# prototype.net
KiCad netlist of a schematic drawn in EAGLE
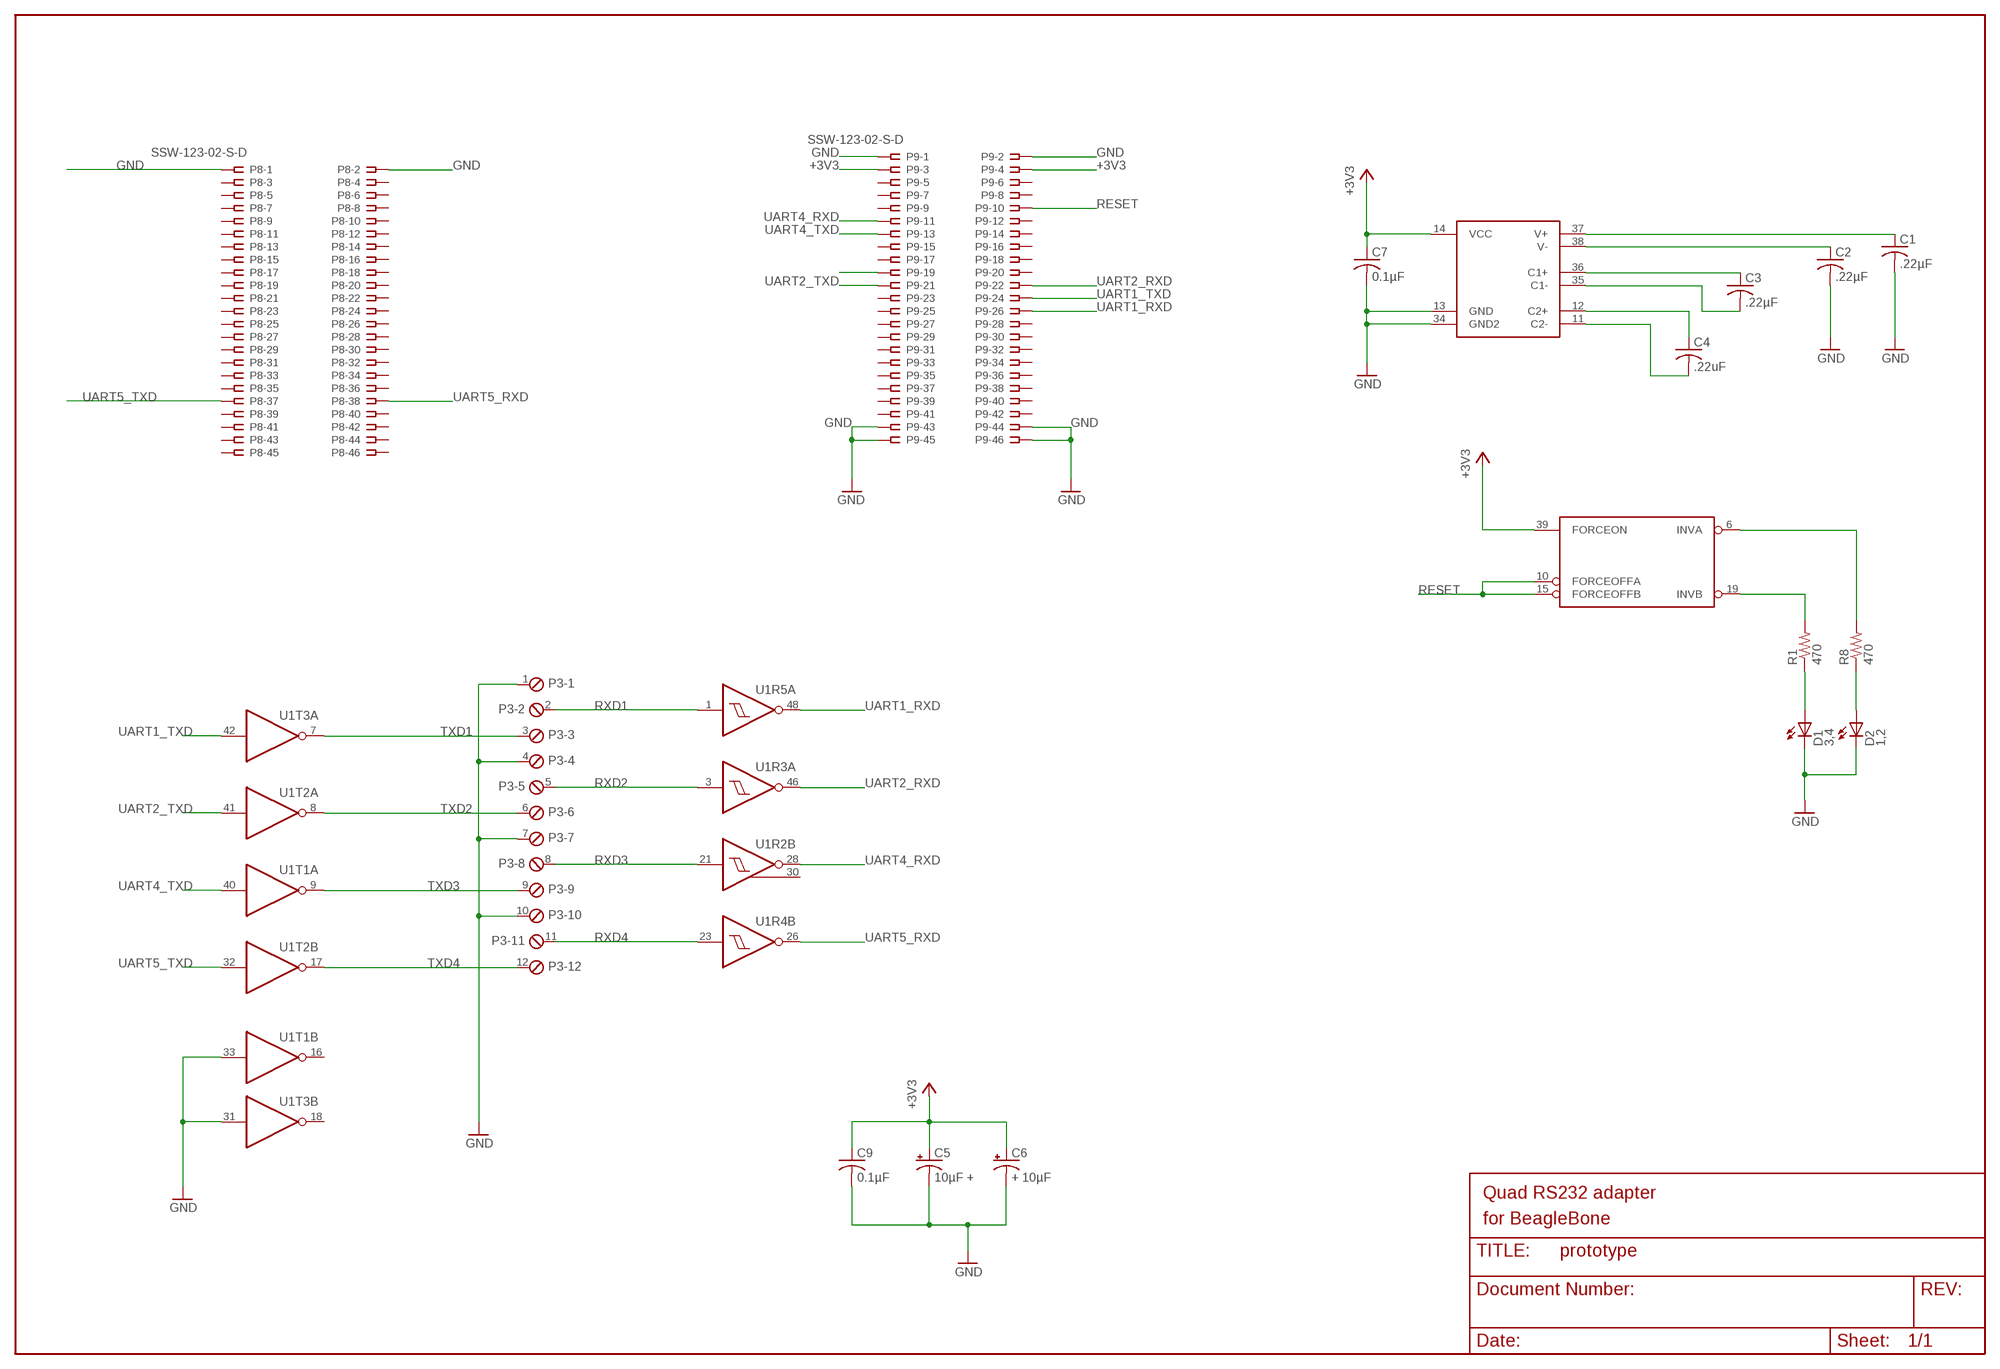
[diagram p0: schematic, sheet 1]

(export (version "E")
  (design (tool "Eeschema 10.0.6"))
  (components
    (comp (ref "C1")
      (value ".22µF")
      (footprint "eagle-import:C0603")
      (libsource (lib "eagle-import") (part "C-USC0603"))
    )
    (comp (ref "C2")
      (value ".22µF")
      (footprint "eagle-import:C0603")
      (libsource (lib "eagle-import") (part "C-USC0603"))
    )
    (comp (ref "C3")
      (value ".22µF")
      (footprint "eagle-import:C0603")
      (libsource (lib "eagle-import") (part "C-USC0603"))
    )
    (comp (ref "C4")
      (value ".22uF")
      (footprint "eagle-import:C0603")
      (libsource (lib "eagle-import") (part "C-USC0603"))
    )
    (comp (ref "C5")
      (value "10µF +")
      (footprint "eagle-import:C1206")
      (libsource (lib "eagle-import") (part "CPOL-USC1206"))
    )
    (comp (ref "C6")
      (value "+ 10µF")
      (footprint "eagle-import:C1206")
      (libsource (lib "eagle-import") (part "CPOL-USC1206"))
    )
    (comp (ref "C7")
      (value "0.1µF")
      (footprint "eagle-import:C0603")
      (libsource (lib "eagle-import") (part "C-USC0603"))
    )
    (comp (ref "C9")
      (value "0.1µF")
      (footprint "eagle-import:C0603")
      (libsource (lib "eagle-import") (part "C-USC0603"))
    )
    (comp (ref "D1")
      (value "3,4")
      (footprint "eagle-import:CHIPLED_0603")
      (libsource (lib "eagle-import") (part "LEDCHIPLED_0603"))
    )
    (comp (ref "D2")
      (value "1,2")
      (footprint "eagle-import:CHIPLED_0603")
      (libsource (lib "eagle-import") (part "LEDCHIPLED_0603"))
    )
    (comp (ref "P3")
      (value "MPT12")
      (footprint "eagle-import:12POL254")
      (libsource (lib "eagle-import") (part "MPT12"))
    )
    (comp (ref "P8")
      (value "SSW-123-02-S-D")
      (footprint "eagle-import:SSW-123-02-S-D")
      (libsource (lib "eagle-import") (part "SSW-123-02-S-D"))
    )
    (comp (ref "P9")
      (value "SSW-123-02-S-D")
      (footprint "eagle-import:SSW-123-02-S-D")
      (libsource (lib "eagle-import") (part "SSW-123-02-S-D"))
    )
    (comp (ref "R1")
      (value "470")
      (footprint "eagle-import:R0603")
      (libsource (lib "eagle-import") (part "R-US_R0603"))
    )
    (comp (ref "R8")
      (value "470")
      (footprint "eagle-import:R0603")
      (libsource (lib "eagle-import") (part "R-US_R0603"))
    )
    (comp (ref "U1")
      (value "SN75C23243")
      (footprint "eagle-import:SSOP48DL")
      (libsource (lib "eagle-import") (part "SN75C23243SN75C23243DL"))
    )
  )
  (nets
    (net (code "1") (name "+3V3") (class "Default")
      (node (ref "C5") (pin "1") (pinfunction "+_1") (pintype "passive"))
      (node (ref "C6") (pin "1") (pinfunction "+_1") (pintype "passive"))
      (node (ref "C7") (pin "1") (pinfunction "1_1") (pintype "passive"))
      (node (ref "C9") (pin "1") (pinfunction "1_1") (pintype "passive"))
      (node (ref "P9") (pin "3") (pinfunction "1_3") (pintype "passive"))
      (node (ref "P9") (pin "4") (pinfunction "1_4") (pintype "passive"))
      (node (ref "U1") (pin "14") (pinfunction "VCC_14") (pintype "power_in"))
      (node (ref "U1") (pin "39") (pinfunction "FORCEON_39") (pintype "input"))
    )
    (net (code "2") (name "/RESET") (class "Default")
      (node (ref "P9") (pin "10") (pinfunction "1_10") (pintype "passive"))
      (node (ref "U1") (pin "10") (pinfunction "FORCEOFFA_10") (pintype "input"))
      (node (ref "U1") (pin "15") (pinfunction "FORCEOFFB_15") (pintype "input"))
    )
    (net (code "3") (name "/RXD1") (class "Default")
      (node (ref "P3") (pin "2") (pinfunction "1_2") (pintype "passive"))
      (node (ref "U1") (pin "1") (pinfunction "I_1") (pintype "input"))
    )
    (net (code "4") (name "/RXD2") (class "Default")
      (node (ref "P3") (pin "5") (pinfunction "1_5") (pintype "passive"))
      (node (ref "U1") (pin "3") (pinfunction "I_3") (pintype "input"))
    )
    (net (code "5") (name "/RXD3") (class "Default")
      (node (ref "P3") (pin "8") (pinfunction "1_8") (pintype "passive"))
      (node (ref "U1") (pin "21") (pinfunction "I_21") (pintype "input"))
    )
    (net (code "6") (name "/RXD4") (class "Default")
      (node (ref "P3") (pin "11") (pinfunction "1_11") (pintype "passive"))
      (node (ref "U1") (pin "23") (pinfunction "I_23") (pintype "input"))
    )
    (net (code "7") (name "/TXD1") (class "Default")
      (node (ref "P3") (pin "3") (pinfunction "1_3") (pintype "passive"))
      (node (ref "U1") (pin "7") (pinfunction "O_7") (pintype "output"))
    )
    (net (code "8") (name "/TXD2") (class "Default")
      (node (ref "P3") (pin "6") (pinfunction "1_6") (pintype "passive"))
      (node (ref "U1") (pin "8") (pinfunction "O_8") (pintype "output"))
    )
    (net (code "9") (name "/TXD3") (class "Default")
      (node (ref "P3") (pin "9") (pinfunction "1_9") (pintype "passive"))
      (node (ref "U1") (pin "9") (pinfunction "O_9") (pintype "output"))
    )
    (net (code "10") (name "/TXD4") (class "Default")
      (node (ref "P3") (pin "12") (pinfunction "1_12") (pintype "passive"))
      (node (ref "U1") (pin "17") (pinfunction "O_17") (pintype "output"))
    )
    (net (code "11") (name "/UART1_RXD") (class "Default")
      (node (ref "P9") (pin "26") (pinfunction "1_26") (pintype "passive"))
      (node (ref "U1") (pin "48") (pinfunction "O_48") (pintype "output"))
    )
    (net (code "12") (name "/UART1_TXD") (class "Default")
      (node (ref "P9") (pin "24") (pinfunction "1_24") (pintype "passive"))
      (node (ref "U1") (pin "42") (pinfunction "I_42") (pintype "input"))
    )
    (net (code "13") (name "/UART2_RXD") (class "Default")
      (node (ref "P9") (pin "22") (pinfunction "1_22") (pintype "passive"))
      (node (ref "U1") (pin "46") (pinfunction "O_46") (pintype "output"))
    )
    (net (code "14") (name "/UART2_TXD") (class "Default")
      (node (ref "P9") (pin "21") (pinfunction "1_21") (pintype "passive"))
      (node (ref "U1") (pin "41") (pinfunction "I_41") (pintype "input"))
    )
    (net (code "15") (name "/UART4_RXD") (class "Default")
      (node (ref "P9") (pin "11") (pinfunction "1_11") (pintype "passive"))
      (node (ref "U1") (pin "28") (pinfunction "O_28") (pintype "output"))
    )
    (net (code "16") (name "/UART4_TXD") (class "Default")
      (node (ref "P9") (pin "13") (pinfunction "1_13") (pintype "passive"))
      (node (ref "U1") (pin "40") (pinfunction "I_40") (pintype "input"))
    )
    (net (code "17") (name "/UART5_RXD") (class "Default")
      (node (ref "P8") (pin "38") (pinfunction "1_38") (pintype "passive"))
      (node (ref "U1") (pin "26") (pinfunction "O_26") (pintype "output"))
    )
    (net (code "18") (name "/UART5_TXD") (class "Default")
      (node (ref "P8") (pin "37") (pinfunction "1_37") (pintype "passive"))
      (node (ref "U1") (pin "32") (pinfunction "I_32") (pintype "input"))
    )
    (net (code "19") (name "GND") (class "Default")
      (node (ref "C1") (pin "2") (pinfunction "2_2") (pintype "passive"))
      (node (ref "C2") (pin "2") (pinfunction "2_2") (pintype "passive"))
      (node (ref "C5") (pin "2") (pinfunction "-_2") (pintype "passive"))
      (node (ref "C6") (pin "2") (pinfunction "-_2") (pintype "passive"))
      (node (ref "C7") (pin "2") (pinfunction "2_2") (pintype "passive"))
      (node (ref "C9") (pin "2") (pinfunction "2_2") (pintype "passive"))
      (node (ref "D1") (pin "C") (pinfunction "C_C") (pintype "passive"))
      (node (ref "D2") (pin "C") (pinfunction "C_C") (pintype "passive"))
      (node (ref "P3") (pin "1") (pinfunction "1_1") (pintype "passive"))
      (node (ref "P3") (pin "10") (pinfunction "1_10") (pintype "passive"))
      (node (ref "P3") (pin "4") (pinfunction "1_4") (pintype "passive"))
      (node (ref "P3") (pin "7") (pinfunction "1_7") (pintype "passive"))
      (node (ref "P8") (pin "1") (pinfunction "1_1") (pintype "passive"))
      (node (ref "P8") (pin "2") (pinfunction "1_2") (pintype "passive"))
      (node (ref "P9") (pin "1") (pinfunction "1_1") (pintype "passive"))
      (node (ref "P9") (pin "2") (pinfunction "1_2") (pintype "passive"))
      (node (ref "P9") (pin "43") (pinfunction "1_43") (pintype "passive"))
      (node (ref "P9") (pin "44") (pinfunction "1_44") (pintype "passive"))
      (node (ref "P9") (pin "45") (pinfunction "1_45") (pintype "passive"))
      (node (ref "P9") (pin "46") (pinfunction "1_46") (pintype "passive"))
      (node (ref "U1") (pin "13") (pinfunction "GND_13") (pintype "power_in"))
      (node (ref "U1") (pin "31") (pinfunction "I_31") (pintype "input"))
      (node (ref "U1") (pin "33") (pinfunction "I_33") (pintype "input"))
      (node (ref "U1") (pin "34") (pinfunction "GND2_34") (pintype "power_in"))
    )
    (net (code "20") (name "Net-(D1-PadA)") (class "Default")
      (node (ref "D1") (pin "A") (pinfunction "A_A") (pintype "passive"))
      (node (ref "R1") (pin "1") (pinfunction "1_1") (pintype "passive"))
    )
    (net (code "21") (name "Net-(D2-PadA)") (class "Default")
      (node (ref "D2") (pin "A") (pinfunction "A_A") (pintype "passive"))
      (node (ref "R8") (pin "1") (pinfunction "1_1") (pintype "passive"))
    )
    (net (code "22") (name "Net-(U1A-INVA)") (class "Default")
      (node (ref "R8") (pin "2") (pinfunction "2_2") (pintype "passive"))
      (node (ref "U1") (pin "6") (pinfunction "INVA_6") (pintype "output"))
    )
    (net (code "23") (name "Net-(U1A-INVB)") (class "Default")
      (node (ref "R1") (pin "2") (pinfunction "2_2") (pintype "passive"))
      (node (ref "U1") (pin "19") (pinfunction "INVB_19") (pintype "output"))
    )
    (net (code "24") (name "Net-(U1B-C1+)") (class "Default")
      (node (ref "C3") (pin "1") (pinfunction "1_1") (pintype "passive"))
      (node (ref "U1") (pin "36") (pinfunction "C1+_36") (pintype "power_in"))
    )
    (net (code "25") (name "Net-(U1B-C1-)") (class "Default")
      (node (ref "C3") (pin "2") (pinfunction "2_2") (pintype "passive"))
      (node (ref "U1") (pin "35") (pinfunction "C1-_35") (pintype "power_in"))
    )
    (net (code "26") (name "Net-(U1B-C2+)") (class "Default")
      (node (ref "C4") (pin "1") (pinfunction "1_1") (pintype "passive"))
      (node (ref "U1") (pin "12") (pinfunction "C2+_12") (pintype "power_in"))
    )
    (net (code "27") (name "Net-(U1B-C2-)") (class "Default")
      (node (ref "C4") (pin "2") (pinfunction "2_2") (pintype "passive"))
      (node (ref "U1") (pin "11") (pinfunction "C2-_11") (pintype "power_in"))
    )
    (net (code "28") (name "Net-(U1B-V+)") (class "Default")
      (node (ref "C1") (pin "1") (pinfunction "1_1") (pintype "passive"))
      (node (ref "U1") (pin "37") (pinfunction "V+_37") (pintype "power_in"))
    )
    (net (code "29") (name "Net-(U1B-V-)") (class "Default")
      (node (ref "C2") (pin "1") (pinfunction "1_1") (pintype "passive"))
      (node (ref "U1") (pin "38") (pinfunction "V-_38") (pintype "power_in"))
    )
    (net (code "30") (name "unconnected-(P8AA-1-Pad33)") (class "Default")
      (node (ref "P8") (pin "33") (pinfunction "1_33") (pintype "passive"))
    )
    (net (code "31") (name "unconnected-(P8AB-1-Pad34)") (class "Default")
      (node (ref "P8") (pin "34") (pinfunction "1_34") (pintype "passive"))
    )
    (net (code "32") (name "unconnected-(P8AC-1-Pad35)") (class "Default")
      (node (ref "P8") (pin "35") (pinfunction "1_35") (pintype "passive"))
    )
    (net (code "33") (name "unconnected-(P8AD-1-Pad36)") (class "Default")
      (node (ref "P8") (pin "36") (pinfunction "1_36") (pintype "passive"))
    )
    (net (code "34") (name "unconnected-(P8AG-1-Pad39)") (class "Default")
      (node (ref "P8") (pin "39") (pinfunction "1_39") (pintype "passive"))
    )
    (net (code "35") (name "unconnected-(P8AH-1-Pad4)") (class "Default")
      (node (ref "P8") (pin "4") (pinfunction "1_4") (pintype "passive"))
    )
    (net (code "36") (name "unconnected-(P8AI-1-Pad40)") (class "Default")
      (node (ref "P8") (pin "40") (pinfunction "1_40") (pintype "passive"))
    )
    (net (code "37") (name "unconnected-(P8AJ-1-Pad41)") (class "Default")
      (node (ref "P8") (pin "41") (pinfunction "1_41") (pintype "passive"))
    )
    (net (code "38") (name "unconnected-(P8AK-1-Pad42)") (class "Default")
      (node (ref "P8") (pin "42") (pinfunction "1_42") (pintype "passive"))
    )
    (net (code "39") (name "unconnected-(P8AL-1-Pad43)") (class "Default")
      (node (ref "P8") (pin "43") (pinfunction "1_43") (pintype "passive"))
    )
    (net (code "40") (name "unconnected-(P8AM-1-Pad44)") (class "Default")
      (node (ref "P8") (pin "44") (pinfunction "1_44") (pintype "passive"))
    )
    (net (code "41") (name "unconnected-(P8AN-1-Pad45)") (class "Default")
      (node (ref "P8") (pin "45") (pinfunction "1_45") (pintype "passive"))
    )
    (net (code "42") (name "unconnected-(P8AO-1-Pad46)") (class "Default")
      (node (ref "P8") (pin "46") (pinfunction "1_46") (pintype "passive"))
    )
    (net (code "43") (name "unconnected-(P8AP-1-Pad5)") (class "Default")
      (node (ref "P8") (pin "5") (pinfunction "1_5") (pintype "passive"))
    )
    (net (code "44") (name "unconnected-(P8AQ-1-Pad6)") (class "Default")
      (node (ref "P8") (pin "6") (pinfunction "1_6") (pintype "passive"))
    )
    (net (code "45") (name "unconnected-(P8AR-1-Pad7)") (class "Default")
      (node (ref "P8") (pin "7") (pinfunction "1_7") (pintype "passive"))
    )
    (net (code "46") (name "unconnected-(P8AS-1-Pad8)") (class "Default")
      (node (ref "P8") (pin "8") (pinfunction "1_8") (pintype "passive"))
    )
    (net (code "47") (name "unconnected-(P8AT-1-Pad9)") (class "Default")
      (node (ref "P8") (pin "9") (pinfunction "1_9") (pintype "passive"))
    )
    (net (code "48") (name "unconnected-(P8B-1-Pad10)") (class "Default")
      (node (ref "P8") (pin "10") (pinfunction "1_10") (pintype "passive"))
    )
    (net (code "49") (name "unconnected-(P8C-1-Pad11)") (class "Default")
      (node (ref "P8") (pin "11") (pinfunction "1_11") (pintype "passive"))
    )
    (net (code "50") (name "unconnected-(P8D-1-Pad12)") (class "Default")
      (node (ref "P8") (pin "12") (pinfunction "1_12") (pintype "passive"))
    )
    (net (code "51") (name "unconnected-(P8E-1-Pad13)") (class "Default")
      (node (ref "P8") (pin "13") (pinfunction "1_13") (pintype "passive"))
    )
    (net (code "52") (name "unconnected-(P8F-1-Pad14)") (class "Default")
      (node (ref "P8") (pin "14") (pinfunction "1_14") (pintype "passive"))
    )
    (net (code "53") (name "unconnected-(P8G-1-Pad15)") (class "Default")
      (node (ref "P8") (pin "15") (pinfunction "1_15") (pintype "passive"))
    )
    (net (code "54") (name "unconnected-(P8H-1-Pad16)") (class "Default")
      (node (ref "P8") (pin "16") (pinfunction "1_16") (pintype "passive"))
    )
    (net (code "55") (name "unconnected-(P8I-1-Pad17)") (class "Default")
      (node (ref "P8") (pin "17") (pinfunction "1_17") (pintype "passive"))
    )
    (net (code "56") (name "unconnected-(P8J-1-Pad18)") (class "Default")
      (node (ref "P8") (pin "18") (pinfunction "1_18") (pintype "passive"))
    )
    (net (code "57") (name "unconnected-(P8K-1-Pad19)") (class "Default")
      (node (ref "P8") (pin "19") (pinfunction "1_19") (pintype "passive"))
    )
    (net (code "58") (name "unconnected-(P8M-1-Pad20)") (class "Default")
      (node (ref "P8") (pin "20") (pinfunction "1_20") (pintype "passive"))
    )
    (net (code "59") (name "unconnected-(P8N-1-Pad21)") (class "Default")
      (node (ref "P8") (pin "21") (pinfunction "1_21") (pintype "passive"))
    )
    (net (code "60") (name "unconnected-(P8O-1-Pad22)") (class "Default")
      (node (ref "P8") (pin "22") (pinfunction "1_22") (pintype "passive"))
    )
    (net (code "61") (name "unconnected-(P8P-1-Pad23)") (class "Default")
      (node (ref "P8") (pin "23") (pinfunction "1_23") (pintype "passive"))
    )
    (net (code "62") (name "unconnected-(P8Q-1-Pad24)") (class "Default")
      (node (ref "P8") (pin "24") (pinfunction "1_24") (pintype "passive"))
    )
    (net (code "63") (name "unconnected-(P8R-1-Pad25)") (class "Default")
      (node (ref "P8") (pin "25") (pinfunction "1_25") (pintype "passive"))
    )
    (net (code "64") (name "unconnected-(P8S-1-Pad26)") (class "Default")
      (node (ref "P8") (pin "26") (pinfunction "1_26") (pintype "passive"))
    )
    (net (code "65") (name "unconnected-(P8T-1-Pad27)") (class "Default")
      (node (ref "P8") (pin "27") (pinfunction "1_27") (pintype "passive"))
    )
    (net (code "66") (name "unconnected-(P8U-1-Pad28)") (class "Default")
      (node (ref "P8") (pin "28") (pinfunction "1_28") (pintype "passive"))
    )
    (net (code "67") (name "unconnected-(P8V-1-Pad29)") (class "Default")
      (node (ref "P8") (pin "29") (pinfunction "1_29") (pintype "passive"))
    )
    (net (code "68") (name "unconnected-(P8W-1-Pad3)") (class "Default")
      (node (ref "P8") (pin "3") (pinfunction "1_3") (pintype "passive"))
    )
    (net (code "69") (name "unconnected-(P8X-1-Pad30)") (class "Default")
      (node (ref "P8") (pin "30") (pinfunction "1_30") (pintype "passive"))
    )
    (net (code "70") (name "unconnected-(P8Y-1-Pad31)") (class "Default")
      (node (ref "P8") (pin "31") (pinfunction "1_31") (pintype "passive"))
    )
    (net (code "71") (name "unconnected-(P8Z-1-Pad32)") (class "Default")
      (node (ref "P8") (pin "32") (pinfunction "1_32") (pintype "passive"))
    )
    (net (code "72") (name "unconnected-(P9AA-1-Pad33)") (class "Default")
      (node (ref "P9") (pin "33") (pinfunction "1_33") (pintype "passive"))
    )
    (net (code "73") (name "unconnected-(P9AB-1-Pad34)") (class "Default")
      (node (ref "P9") (pin "34") (pinfunction "1_34") (pintype "passive"))
    )
    (net (code "74") (name "unconnected-(P9AC-1-Pad35)") (class "Default")
      (node (ref "P9") (pin "35") (pinfunction "1_35") (pintype "passive"))
    )
    (net (code "75") (name "unconnected-(P9AD-1-Pad36)") (class "Default")
      (node (ref "P9") (pin "36") (pinfunction "1_36") (pintype "passive"))
    )
    (net (code "76") (name "unconnected-(P9AE-1-Pad37)") (class "Default")
      (node (ref "P9") (pin "37") (pinfunction "1_37") (pintype "passive"))
    )
    (net (code "77") (name "unconnected-(P9AF-1-Pad38)") (class "Default")
      (node (ref "P9") (pin "38") (pinfunction "1_38") (pintype "passive"))
    )
    (net (code "78") (name "unconnected-(P9AG-1-Pad39)") (class "Default")
      (node (ref "P9") (pin "39") (pinfunction "1_39") (pintype "passive"))
    )
    (net (code "79") (name "unconnected-(P9AI-1-Pad40)") (class "Default")
      (node (ref "P9") (pin "40") (pinfunction "1_40") (pintype "passive"))
    )
    (net (code "80") (name "unconnected-(P9AJ-1-Pad41)") (class "Default")
      (node (ref "P9") (pin "41") (pinfunction "1_41") (pintype "passive"))
    )
    (net (code "81") (name "unconnected-(P9AK-1-Pad42)") (class "Default")
      (node (ref "P9") (pin "42") (pinfunction "1_42") (pintype "passive"))
    )
    (net (code "82") (name "unconnected-(P9AP-1-Pad5)") (class "Default")
      (node (ref "P9") (pin "5") (pinfunction "1_5") (pintype "passive"))
    )
    (net (code "83") (name "unconnected-(P9AQ-1-Pad6)") (class "Default")
      (node (ref "P9") (pin "6") (pinfunction "1_6") (pintype "passive"))
    )
    (net (code "84") (name "unconnected-(P9AR-1-Pad7)") (class "Default")
      (node (ref "P9") (pin "7") (pinfunction "1_7") (pintype "passive"))
    )
    (net (code "85") (name "unconnected-(P9AS-1-Pad8)") (class "Default")
      (node (ref "P9") (pin "8") (pinfunction "1_8") (pintype "passive"))
    )
    (net (code "86") (name "unconnected-(P9AT-1-Pad9)") (class "Default")
      (node (ref "P9") (pin "9") (pinfunction "1_9") (pintype "passive"))
    )
    (net (code "87") (name "unconnected-(P9D-1-Pad12)") (class "Default")
      (node (ref "P9") (pin "12") (pinfunction "1_12") (pintype "passive"))
    )
    (net (code "88") (name "unconnected-(P9F-1-Pad14)") (class "Default")
      (node (ref "P9") (pin "14") (pinfunction "1_14") (pintype "passive"))
    )
    (net (code "89") (name "unconnected-(P9G-1-Pad15)") (class "Default")
      (node (ref "P9") (pin "15") (pinfunction "1_15") (pintype "passive"))
    )
    (net (code "90") (name "unconnected-(P9H-1-Pad16)") (class "Default")
      (node (ref "P9") (pin "16") (pinfunction "1_16") (pintype "passive"))
    )
    (net (code "91") (name "unconnected-(P9I-1-Pad17)") (class "Default")
      (node (ref "P9") (pin "17") (pinfunction "1_17") (pintype "passive"))
    )
    (net (code "92") (name "unconnected-(P9J-1-Pad18)") (class "Default")
      (node (ref "P9") (pin "18") (pinfunction "1_18") (pintype "passive"))
    )
    (net (code "93") (name "unconnected-(P9K-1-Pad19)") (class "Default")
      (node (ref "P9") (pin "19") (pinfunction "1_19") (pintype "passive"))
    )
    (net (code "94") (name "unconnected-(P9M-1-Pad20)") (class "Default")
      (node (ref "P9") (pin "20") (pinfunction "1_20") (pintype "passive"))
    )
    (net (code "95") (name "unconnected-(P9P-1-Pad23)") (class "Default")
      (node (ref "P9") (pin "23") (pinfunction "1_23") (pintype "passive"))
    )
    (net (code "96") (name "unconnected-(P9R-1-Pad25)") (class "Default")
      (node (ref "P9") (pin "25") (pinfunction "1_25") (pintype "passive"))
    )
    (net (code "97") (name "unconnected-(P9T-1-Pad27)") (class "Default")
      (node (ref "P9") (pin "27") (pinfunction "1_27") (pintype "passive"))
    )
    (net (code "98") (name "unconnected-(P9U-1-Pad28)") (class "Default")
      (node (ref "P9") (pin "28") (pinfunction "1_28") (pintype "passive"))
    )
    (net (code "99") (name "unconnected-(P9V-1-Pad29)") (class "Default")
      (node (ref "P9") (pin "29") (pinfunction "1_29") (pintype "passive"))
    )
    (net (code "100") (name "unconnected-(P9X-1-Pad30)") (class "Default")
      (node (ref "P9") (pin "30") (pinfunction "1_30") (pintype "passive"))
    )
    (net (code "101") (name "unconnected-(P9Y-1-Pad31)") (class "Default")
      (node (ref "P9") (pin "31") (pinfunction "1_31") (pintype "passive"))
    )
    (net (code "102") (name "unconnected-(P9Z-1-Pad32)") (class "Default")
      (node (ref "P9") (pin "32") (pinfunction "1_32") (pintype "passive"))
    )
    (net (code "103") (name "unconnected-(U1F-OINV-Pad30)") (class "Default")
      (node (ref "U1") (pin "30") (pinfunction "OINV_30") (pintype "output"))
    )
    (net (code "104") (name "unconnected-(U1N-O-Pad16)") (class "Default")
      (node (ref "U1") (pin "16") (pinfunction "O_16") (pintype "output"))
    )
    (net (code "105") (name "unconnected-(U1R-O-Pad18)") (class "Default")
      (node (ref "U1") (pin "18") (pinfunction "O_18") (pintype "output"))
    )
  )
)
